# Output.net
KiCad netlist of a schematic drawn in Altium Designer
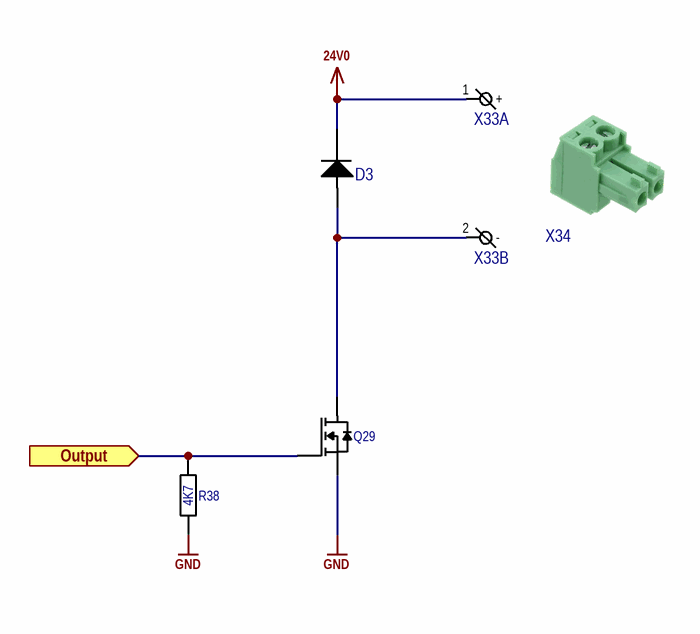
[diagram p0: Output.SchDoc]

(export (version "E")
  (design (tool "Eeschema 10.0.6"))
  (components
    (comp (ref "D3")
      (value "D")
      (footprint "SOT23-3")
      (description "DIODE SCHOTTKY 70V 70MA SOT23-3")
      (fields
        (field (name "02. DISTRIBUTOR PART NUMBER") "BAS70LT1GOSCT-ND")
        (field (name "07. MANUFACTURER  PART NUMBER") "BAS70LT1G")
        (field (name "13. CREATED DATE/NAME") "AUG 2018 / Hören")
      )
      (libsource (lib "tom") (part "HSMS-2800-TR1G"))
    )
    (comp (ref "Q29")
      (value "Q")
      (footprint "SOIC-8_MOSFET")
      (description "Transistor: N-MOSFET; unipolar; 60V; 8,5A; 2W; SO8")
      (fields (field (name "02. DISTRIBUTOR PART NUMBER") "AO4266E"))
      (libsource (lib "PCB-Tester-Board-V1") (part "AO4266E"))
    )
    (comp (ref "R38")
      (value "4K7")
      (footprint "R0603 Reflow")
      (description "RES SMD 4.7K OHM 1% 1/10W 0603")
      (fields
        (field (name "TOLERANCE") "±1%")
        (field (name "02. DISTRIBUTOR PART NUMBER") "311-4.70KHRCT-ND")
        (field (name "13. CREATED DATE/NAME") "AUG2018/Hören")
      )
      (libsource (lib "chickenfood") (part "R"))
    )
    (comp (ref "X33")
      (value "X")
      (footprint "691322310002")
      (description "TERM BLOCK HDR 2POS 90DEG 3.81MM")
      (fields
        (field (name "02. DISTRIBUTOR PART NUMBER") "732-2088-ND")
        (field (name "07. MANUFACTURER  PART NUMBER") "691322310002")
        (field (name "13. CREATED DATE/NAME") "??? / Hören")
      )
      (libsource (lib "Connectors") (part "691322310002"))
    )
    (comp (ref "X34")
      (value "X")
      (footprint "691361300002")
      (description "TERM BLOCK PLUG 2POS STR 3.81MM")
      (fields
        (field (name "02. DISTRIBUTOR PART NUMBER") "732-2076-ND")
        (field (name "07. MANUFACTURER  PART NUMBER") "691361300002")
        (field (name "13. CREATED DATE/NAME") "??? / Hören")
      )
      (libsource (lib "PCB-Tester-Board-V1") (part "691361300002"))
    )
  )
  (nets
    (net (code "1") (name "/Output") (class "Default")
      (node (ref "Q29") (pin "1") (pinfunction "G_1") (pintype "passive"))
      (node (ref "R38") (pin "2") (pinfunction "2_2") (pintype "passive"))
    )
    (net (code "2") (name "24V0") (class "Default")
      (node (ref "D3") (pin "3") (pinfunction "C_3") (pintype "passive"))
      (node (ref "X33") (pin "1") (pinfunction "+_1") (pintype "passive"))
    )
    (net (code "3") (name "GND") (class "Default")
      (node (ref "Q29") (pin "2") (pinfunction "S_2") (pintype "passive"))
      (node (ref "R38") (pin "1") (pinfunction "1_1") (pintype "passive"))
    )
    (net (code "4") (name "Net-(D3-A)") (class "Default")
      (node (ref "D3") (pin "1") (pinfunction "A_1") (pintype "passive"))
      (node (ref "Q29") (pin "3") (pinfunction "D_3") (pintype "passive"))
      (node (ref "X33") (pin "2") (pinfunction "-_2") (pintype "passive"))
    )
  )
)
